# UART_LOGIC.net
KiCad netlist of a schematic drawn in Altium Designer
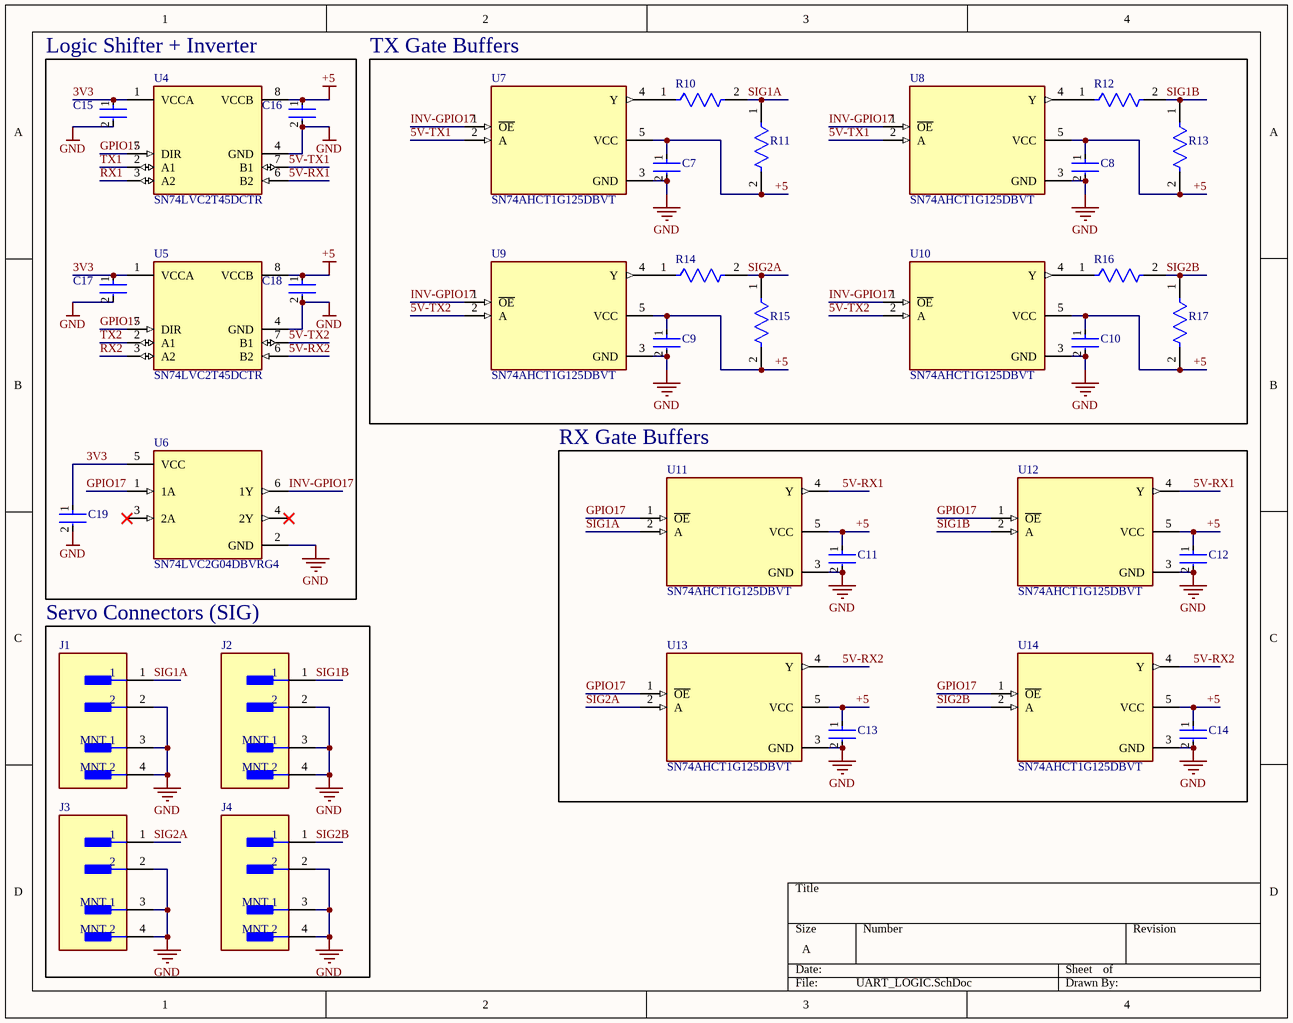
[diagram p0: UART_LOGIC.SchDoc]

(export (version "E")
  (design (tool "Eeschema 10.0.6"))
  (components
    (comp (ref "C7")
      (value "CC0805KRX7R9BB104")
      (footprint "FP-CC0805-0_85-MFG")
      (description "CAP CER 0.1UF 50V X7R 0805")
      (fields (field (name "TOLERANCE") "0.1") (field (name "MANUFACTURER") "Yageo"))
      (libsource (lib "Altium Content Vault") (part "11868f565c42a9108669ba33697ecf6"))
    )
    (comp (ref "C8")
      (value "CC0805KRX7R9BB104")
      (footprint "FP-CC0805-0_85-MFG")
      (description "CAP CER 0.1UF 50V X7R 0805")
      (fields (field (name "TOLERANCE") "0.1") (field (name "MANUFACTURER") "Yageo"))
      (libsource (lib "Altium Content Vault") (part "11868f565c42a9108669ba33697ecf6"))
    )
    (comp (ref "C9")
      (value "CC0805KRX7R9BB104")
      (footprint "FP-CC0805-0_85-MFG")
      (description "CAP CER 0.1UF 50V X7R 0805")
      (fields (field (name "TOLERANCE") "0.1") (field (name "MANUFACTURER") "Yageo"))
      (libsource (lib "Altium Content Vault") (part "11868f565c42a9108669ba33697ecf6"))
    )
    (comp (ref "C10")
      (value "CC0805KRX7R9BB104")
      (footprint "FP-CC0805-0_85-MFG")
      (description "CAP CER 0.1UF 50V X7R 0805")
      (fields (field (name "TOLERANCE") "0.1") (field (name "MANUFACTURER") "Yageo"))
      (libsource (lib "Altium Content Vault") (part "11868f565c42a9108669ba33697ecf6"))
    )
    (comp (ref "C11")
      (value "CC0805KRX7R9BB104")
      (footprint "FP-CC0805-0_85-MFG")
      (description "CAP CER 0.1UF 50V X7R 0805")
      (fields (field (name "TOLERANCE") "0.1") (field (name "MANUFACTURER") "Yageo"))
      (libsource (lib "Altium Content Vault") (part "11868f565c42a9108669ba33697ecf6"))
    )
    (comp (ref "C12")
      (value "CC0805KRX7R9BB104")
      (footprint "FP-CC0805-0_85-MFG")
      (description "CAP CER 0.1UF 50V X7R 0805")
      (fields (field (name "TOLERANCE") "0.1") (field (name "MANUFACTURER") "Yageo"))
      (libsource (lib "Altium Content Vault") (part "11868f565c42a9108669ba33697ecf6"))
    )
    (comp (ref "C13")
      (value "CC0805KRX7R9BB104")
      (footprint "FP-CC0805-0_85-MFG")
      (description "CAP CER 0.1UF 50V X7R 0805")
      (fields (field (name "TOLERANCE") "0.1") (field (name "MANUFACTURER") "Yageo"))
      (libsource (lib "Altium Content Vault") (part "11868f565c42a9108669ba33697ecf6"))
    )
    (comp (ref "C14")
      (value "CC0805KRX7R9BB104")
      (footprint "FP-CC0805-0_85-MFG")
      (description "CAP CER 0.1UF 50V X7R 0805")
      (fields (field (name "TOLERANCE") "0.1") (field (name "MANUFACTURER") "Yageo"))
      (libsource (lib "Altium Content Vault") (part "11868f565c42a9108669ba33697ecf6"))
    )
    (comp (ref "C15")
      (value "CC0805KRX7R9BB104")
      (footprint "FP-CC0805-0_85-MFG")
      (description "CAP CER 0.1UF 50V X7R 0805")
      (fields (field (name "TOLERANCE") "0.1") (field (name "MANUFACTURER") "Yageo"))
      (libsource (lib "Altium Content Vault") (part "11868f565c42a9108669ba33697ecf6"))
    )
    (comp (ref "C16")
      (value "CC0805KRX7R9BB104")
      (footprint "FP-CC0805-0_85-MFG")
      (description "CAP CER 0.1UF 50V X7R 0805")
      (fields (field (name "TOLERANCE") "0.1") (field (name "MANUFACTURER") "Yageo"))
      (libsource (lib "Altium Content Vault") (part "11868f565c42a9108669ba33697ecf6"))
    )
    (comp (ref "C17")
      (value "CC0805KRX7R9BB104")
      (footprint "FP-CC0805-0_85-MFG")
      (description "CAP CER 0.1UF 50V X7R 0805")
      (fields (field (name "TOLERANCE") "0.1") (field (name "MANUFACTURER") "Yageo"))
      (libsource (lib "Altium Content Vault") (part "11868f565c42a9108669ba33697ecf6"))
    )
    (comp (ref "C18")
      (value "CC0805KRX7R9BB104")
      (footprint "FP-CC0805-0_85-MFG")
      (description "CAP CER 0.1UF 50V X7R 0805")
      (fields (field (name "TOLERANCE") "0.1") (field (name "MANUFACTURER") "Yageo"))
      (libsource (lib "Altium Content Vault") (part "11868f565c42a9108669ba33697ecf6"))
    )
    (comp (ref "C19")
      (value "CC0805KRX7R9BB104")
      (footprint "FP-CC0805-0_85-MFG")
      (description "CAP CER 0.1UF 50V X7R 0805")
      (fields (field (name "TOLERANCE") "0.1") (field (name "MANUFACTURER") "Yageo"))
      (libsource (lib "Altium Content Vault") (part "11868f565c42a9108669ba33697ecf6"))
    )
    (comp (ref "J1")
      (value "BM02B-SRSS-TBT(LF)(SN)")
      (footprint "FP-BM02B-SRSS-TBT_LF_SN-MFG")
      (description "CONN WIRE HDR 2POS 1MM STSMD")
      (libsource (lib "Altium Content Vault") (part "029478cb6d4f2fad0cd2a245525ee6d"))
    )
    (comp (ref "J2")
      (value "BM02B-SRSS-TBT(LF)(SN)")
      (footprint "FP-BM02B-SRSS-TBT_LF_SN-MFG")
      (description "CONN WIRE HDR 2POS 1MM STSMD")
      (libsource (lib "Altium Content Vault") (part "029478cb6d4f2fad0cd2a245525ee6d"))
    )
    (comp (ref "J3")
      (value "BM02B-SRSS-TBT(LF)(SN)")
      (footprint "FP-BM02B-SRSS-TBT_LF_SN-MFG")
      (description "CONN WIRE HDR 2POS 1MM STSMD")
      (libsource (lib "Altium Content Vault") (part "029478cb6d4f2fad0cd2a245525ee6d"))
    )
    (comp (ref "J4")
      (value "BM02B-SRSS-TBT(LF)(SN)")
      (footprint "FP-BM02B-SRSS-TBT_LF_SN-MFG")
      (description "CONN WIRE HDR 2POS 1MM STSMD")
      (libsource (lib "Altium Content Vault") (part "029478cb6d4f2fad0cd2a245525ee6d"))
    )
    (comp (ref "R10")
      (value "RMCF0603FG47R0")
      (footprint "FP-RMCF0603-IPC_A")
      (description "47Ω ±1% 0.1W 0603 Thick Film Chip Resistor AEC-Q200 compliant")
      (libsource (lib "Altium Content Vault") (part "1029c3af85768c4190bb7ad29bc67b5"))
    )
    (comp (ref "R11")
      (value "RC0603FR-0710KL")
      (footprint "FP-RC0603-0_55-IPC_C")
      (description "RES 10K OHM 1% 1/10W 0603")
      (fields (field (name "TOLERANCE") "1%"))
      (libsource (lib "Altium Content Vault") (part "1029c3af85768c4190bb7ad29bc67b5"))
    )
    (comp (ref "R12")
      (value "RMCF0603FG47R0")
      (footprint "FP-RMCF0603-IPC_A")
      (description "47Ω ±1% 0.1W 0603 Thick Film Chip Resistor AEC-Q200 compliant")
      (libsource (lib "Altium Content Vault") (part "1029c3af85768c4190bb7ad29bc67b5"))
    )
    (comp (ref "R13")
      (value "RC0603FR-0710KL")
      (footprint "FP-RC0603-0_55-IPC_C")
      (description "RES 10K OHM 1% 1/10W 0603")
      (fields (field (name "TOLERANCE") "1%"))
      (libsource (lib "Altium Content Vault") (part "1029c3af85768c4190bb7ad29bc67b5"))
    )
    (comp (ref "R14")
      (value "RMCF0603FG47R0")
      (footprint "FP-RMCF0603-IPC_A")
      (description "47Ω ±1% 0.1W 0603 Thick Film Chip Resistor AEC-Q200 compliant")
      (libsource (lib "Altium Content Vault") (part "1029c3af85768c4190bb7ad29bc67b5"))
    )
    (comp (ref "R15")
      (value "RC0603FR-0710KL")
      (footprint "FP-RC0603-0_55-IPC_C")
      (description "RES 10K OHM 1% 1/10W 0603")
      (fields (field (name "TOLERANCE") "1%"))
      (libsource (lib "Altium Content Vault") (part "1029c3af85768c4190bb7ad29bc67b5"))
    )
    (comp (ref "R16")
      (value "RMCF0603FG47R0")
      (footprint "FP-RMCF0603-IPC_A")
      (description "47Ω ±1% 0.1W 0603 Thick Film Chip Resistor AEC-Q200 compliant")
      (libsource (lib "Altium Content Vault") (part "1029c3af85768c4190bb7ad29bc67b5"))
    )
    (comp (ref "R17")
      (value "RC0603FR-0710KL")
      (footprint "FP-RC0603-0_55-IPC_C")
      (description "RES 10K OHM 1% 1/10W 0603")
      (fields (field (name "TOLERANCE") "1%"))
      (libsource (lib "Altium Content Vault") (part "1029c3af85768c4190bb7ad29bc67b5"))
    )
    (comp (ref "U4")
      (value "SN74LVC2T45DCTR")
      (footprint "FP-DCT0008A-IPC_C")
      (libsource (lib "Bryan Heddle") (part "271d40e9c72c712db4b2912206096bb"))
    )
    (comp (ref "U5")
      (value "SN74LVC2T45DCTR")
      (footprint "FP-DCT0008A-IPC_C")
      (libsource (lib "Bryan Heddle") (part "271d40e9c72c712db4b2912206096bb"))
    )
    (comp (ref "U6")
      (value "SN74LVC2G04DBVRG4")
      (footprint "FP-DBV0006A-MFG")
      (description "IC INVERTER 2CH 2-INP SOT23-6")
      (libsource (lib "Altium Content Vault") (part "9dfbf26b1eab2647ff4a890ff2a17ee"))
    )
    (comp (ref "U7")
      (value "SN74AHCT1G125DBVT")
      (footprint "SOT95P280X145-5N")
      (description "Single 4.5-V to 5.5-V buffer with TTL-compatible CMOS inputs and 3-state outputs")
      (fields (field (name "MF") "Texas Instruments"))
      (libsource (lib "Bryan Heddle") (part "SN74AHCT1G125DBVT"))
    )
    (comp (ref "U8")
      (value "SN74AHCT1G125DBVT")
      (footprint "SOT95P280X145-5N")
      (description "Single 4.5-V to 5.5-V buffer with TTL-compatible CMOS inputs and 3-state outputs")
      (fields (field (name "MF") "Texas Instruments"))
      (libsource (lib "Bryan Heddle") (part "SN74AHCT1G125DBVT"))
    )
    (comp (ref "U9")
      (value "SN74AHCT1G125DBVT")
      (footprint "SOT95P280X145-5N")
      (description "Single 4.5-V to 5.5-V buffer with TTL-compatible CMOS inputs and 3-state outputs")
      (fields (field (name "MF") "Texas Instruments"))
      (libsource (lib "Bryan Heddle") (part "SN74AHCT1G125DBVT"))
    )
    (comp (ref "U10")
      (value "SN74AHCT1G125DBVT")
      (footprint "SOT95P280X145-5N")
      (description "Single 4.5-V to 5.5-V buffer with TTL-compatible CMOS inputs and 3-state outputs")
      (fields (field (name "MF") "Texas Instruments"))
      (libsource (lib "Bryan Heddle") (part "SN74AHCT1G125DBVT"))
    )
    (comp (ref "U11")
      (value "SN74AHCT1G125DBVT")
      (footprint "SOT95P280X145-5N")
      (description "Single 4.5-V to 5.5-V buffer with TTL-compatible CMOS inputs and 3-state outputs")
      (fields (field (name "MF") "Texas Instruments"))
      (libsource (lib "Bryan Heddle") (part "SN74AHCT1G125DBVT"))
    )
    (comp (ref "U12")
      (value "SN74AHCT1G125DBVT")
      (footprint "SOT95P280X145-5N")
      (description "Single 4.5-V to 5.5-V buffer with TTL-compatible CMOS inputs and 3-state outputs")
      (fields (field (name "MF") "Texas Instruments"))
      (libsource (lib "Bryan Heddle") (part "SN74AHCT1G125DBVT"))
    )
    (comp (ref "U13")
      (value "SN74AHCT1G125DBVT")
      (footprint "SOT95P280X145-5N")
      (description "Single 4.5-V to 5.5-V buffer with TTL-compatible CMOS inputs and 3-state outputs")
      (fields (field (name "MF") "Texas Instruments"))
      (libsource (lib "Bryan Heddle") (part "SN74AHCT1G125DBVT"))
    )
    (comp (ref "U14")
      (value "SN74AHCT1G125DBVT")
      (footprint "SOT95P280X145-5N")
      (description "Single 4.5-V to 5.5-V buffer with TTL-compatible CMOS inputs and 3-state outputs")
      (fields (field (name "MF") "Texas Instruments"))
      (libsource (lib "Bryan Heddle") (part "SN74AHCT1G125DBVT"))
    )
  )
  (nets
    (net (code "1") (name "+5") (class "Default")
      (node (ref "C10") (pin "1") (pinfunction "1_1") (pintype "passive"))
      (node (ref "C11") (pin "1") (pinfunction "1_1") (pintype "passive"))
      (node (ref "C12") (pin "1") (pinfunction "1_1") (pintype "passive"))
      (node (ref "C13") (pin "1") (pinfunction "1_1") (pintype "passive"))
      (node (ref "C14") (pin "1") (pinfunction "1_1") (pintype "passive"))
      (node (ref "C16") (pin "1") (pinfunction "1_1") (pintype "passive"))
      (node (ref "C18") (pin "1") (pinfunction "1_1") (pintype "passive"))
      (node (ref "C7") (pin "1") (pinfunction "1_1") (pintype "passive"))
      (node (ref "C8") (pin "1") (pinfunction "1_1") (pintype "passive"))
      (node (ref "C9") (pin "1") (pinfunction "1_1") (pintype "passive"))
      (node (ref "R11") (pin "2") (pinfunction "2_2") (pintype "passive"))
      (node (ref "R13") (pin "2") (pinfunction "2_2") (pintype "passive"))
      (node (ref "R15") (pin "2") (pinfunction "2_2") (pintype "passive"))
      (node (ref "R17") (pin "2") (pinfunction "2_2") (pintype "passive"))
      (node (ref "U10") (pin "5") (pinfunction "VCC_5") (pintype "power_in"))
      (node (ref "U11") (pin "5") (pinfunction "VCC_5") (pintype "power_in"))
      (node (ref "U12") (pin "5") (pinfunction "VCC_5") (pintype "power_in"))
      (node (ref "U13") (pin "5") (pinfunction "VCC_5") (pintype "power_in"))
      (node (ref "U14") (pin "5") (pinfunction "VCC_5") (pintype "power_in"))
      (node (ref "U4") (pin "8") (pinfunction "VCCB_8") (pintype "power_in"))
      (node (ref "U5") (pin "8") (pinfunction "VCCB_8") (pintype "power_in"))
      (node (ref "U7") (pin "5") (pinfunction "VCC_5") (pintype "power_in"))
      (node (ref "U8") (pin "5") (pinfunction "VCC_5") (pintype "power_in"))
      (node (ref "U9") (pin "5") (pinfunction "VCC_5") (pintype "power_in"))
    )
    (net (code "2") (name "/3V3") (class "Default")
      (node (ref "C15") (pin "1") (pinfunction "1_1") (pintype "passive"))
      (node (ref "C17") (pin "1") (pinfunction "1_1") (pintype "passive"))
      (node (ref "C19") (pin "1") (pinfunction "1_1") (pintype "passive"))
      (node (ref "U4") (pin "1") (pinfunction "VCCA_1") (pintype "power_in"))
      (node (ref "U5") (pin "1") (pinfunction "VCCA_1") (pintype "power_in"))
      (node (ref "U6") (pin "5") (pinfunction "VCC_5") (pintype "power_in"))
    )
    (net (code "3") (name "/5V-RX1") (class "Default")
      (node (ref "U11") (pin "4") (pinfunction "Y_4") (pintype "output"))
      (node (ref "U12") (pin "4") (pinfunction "Y_4") (pintype "output"))
      (node (ref "U4") (pin "6") (pinfunction "B2_6") (pintype "input"))
    )
    (net (code "4") (name "/5V-RX2") (class "Default")
      (node (ref "U13") (pin "4") (pinfunction "Y_4") (pintype "output"))
      (node (ref "U14") (pin "4") (pinfunction "Y_4") (pintype "output"))
      (node (ref "U5") (pin "6") (pinfunction "B2_6") (pintype "input"))
    )
    (net (code "5") (name "/5V-TX1") (class "Default")
      (node (ref "U4") (pin "7") (pinfunction "B1_7") (pintype "bidirectional"))
      (node (ref "U7") (pin "2") (pinfunction "A_2") (pintype "input"))
      (node (ref "U8") (pin "2") (pinfunction "A_2") (pintype "input"))
    )
    (net (code "6") (name "/5V-TX2") (class "Default")
      (node (ref "U10") (pin "2") (pinfunction "A_2") (pintype "input"))
      (node (ref "U5") (pin "7") (pinfunction "B1_7") (pintype "bidirectional"))
      (node (ref "U9") (pin "2") (pinfunction "A_2") (pintype "input"))
    )
    (net (code "7") (name "/GPIO17") (class "Default")
      (node (ref "U11") (pin "1") (pinfunction "~{OE}_1") (pintype "input"))
      (node (ref "U12") (pin "1") (pinfunction "~{OE}_1") (pintype "input"))
      (node (ref "U13") (pin "1") (pinfunction "~{OE}_1") (pintype "input"))
      (node (ref "U14") (pin "1") (pinfunction "~{OE}_1") (pintype "input"))
      (node (ref "U4") (pin "5") (pinfunction "DIR_5") (pintype "input"))
      (node (ref "U5") (pin "5") (pinfunction "DIR_5") (pintype "input"))
      (node (ref "U6") (pin "1") (pinfunction "1A_1") (pintype "input"))
    )
    (net (code "8") (name "/INV-GPIO17") (class "Default")
      (node (ref "U10") (pin "1") (pinfunction "~{OE}_1") (pintype "input"))
      (node (ref "U6") (pin "6") (pinfunction "1Y_6") (pintype "output"))
      (node (ref "U7") (pin "1") (pinfunction "~{OE}_1") (pintype "input"))
      (node (ref "U8") (pin "1") (pinfunction "~{OE}_1") (pintype "input"))
      (node (ref "U9") (pin "1") (pinfunction "~{OE}_1") (pintype "input"))
    )
    (net (code "9") (name "/RX1") (class "Default")
      (node (ref "U4") (pin "3") (pinfunction "A2_3") (pintype "bidirectional"))
    )
    (net (code "10") (name "/RX2") (class "Default")
      (node (ref "U5") (pin "3") (pinfunction "A2_3") (pintype "bidirectional"))
    )
    (net (code "11") (name "/SIG1A") (class "Default")
      (node (ref "J1") (pin "1") (pinfunction "1_1") (pintype "passive"))
      (node (ref "R10") (pin "2") (pinfunction "2_2") (pintype "passive"))
      (node (ref "R11") (pin "1") (pinfunction "1_1") (pintype "passive"))
      (node (ref "U11") (pin "2") (pinfunction "A_2") (pintype "input"))
    )
    (net (code "12") (name "/SIG1B") (class "Default")
      (node (ref "J2") (pin "1") (pinfunction "1_1") (pintype "passive"))
      (node (ref "R12") (pin "2") (pinfunction "2_2") (pintype "passive"))
      (node (ref "R13") (pin "1") (pinfunction "1_1") (pintype "passive"))
      (node (ref "U12") (pin "2") (pinfunction "A_2") (pintype "input"))
    )
    (net (code "13") (name "/SIG2A") (class "Default")
      (node (ref "J3") (pin "1") (pinfunction "1_1") (pintype "passive"))
      (node (ref "R14") (pin "2") (pinfunction "2_2") (pintype "passive"))
      (node (ref "R15") (pin "1") (pinfunction "1_1") (pintype "passive"))
      (node (ref "U13") (pin "2") (pinfunction "A_2") (pintype "input"))
    )
    (net (code "14") (name "/SIG2B") (class "Default")
      (node (ref "J4") (pin "1") (pinfunction "1_1") (pintype "passive"))
      (node (ref "R16") (pin "2") (pinfunction "2_2") (pintype "passive"))
      (node (ref "R17") (pin "1") (pinfunction "1_1") (pintype "passive"))
      (node (ref "U14") (pin "2") (pinfunction "A_2") (pintype "input"))
    )
    (net (code "15") (name "/TX1") (class "Default")
      (node (ref "U4") (pin "2") (pinfunction "A1_2") (pintype "bidirectional"))
    )
    (net (code "16") (name "/TX2") (class "Default")
      (node (ref "U5") (pin "2") (pinfunction "A1_2") (pintype "bidirectional"))
    )
    (net (code "17") (name "GND") (class "Default")
      (node (ref "C10") (pin "2") (pinfunction "2_2") (pintype "passive"))
      (node (ref "C11") (pin "2") (pinfunction "2_2") (pintype "passive"))
      (node (ref "C12") (pin "2") (pinfunction "2_2") (pintype "passive"))
      (node (ref "C13") (pin "2") (pinfunction "2_2") (pintype "passive"))
      (node (ref "C14") (pin "2") (pinfunction "2_2") (pintype "passive"))
      (node (ref "C15") (pin "2") (pinfunction "2_2") (pintype "passive"))
      (node (ref "C16") (pin "2") (pinfunction "2_2") (pintype "passive"))
      (node (ref "C17") (pin "2") (pinfunction "2_2") (pintype "passive"))
      (node (ref "C18") (pin "2") (pinfunction "2_2") (pintype "passive"))
      (node (ref "C19") (pin "2") (pinfunction "2_2") (pintype "passive"))
      (node (ref "C7") (pin "2") (pinfunction "2_2") (pintype "passive"))
      (node (ref "C8") (pin "2") (pinfunction "2_2") (pintype "passive"))
      (node (ref "C9") (pin "2") (pinfunction "2_2") (pintype "passive"))
      (node (ref "J1") (pin "2") (pinfunction "2_2") (pintype "passive"))
      (node (ref "J1") (pin "3") (pinfunction "MNT_1_3") (pintype "passive"))
      (node (ref "J1") (pin "4") (pinfunction "MNT_2_4") (pintype "passive"))
      (node (ref "J2") (pin "2") (pinfunction "2_2") (pintype "passive"))
      (node (ref "J2") (pin "3") (pinfunction "MNT_1_3") (pintype "passive"))
      (node (ref "J2") (pin "4") (pinfunction "MNT_2_4") (pintype "passive"))
      (node (ref "J3") (pin "2") (pinfunction "2_2") (pintype "passive"))
      (node (ref "J3") (pin "3") (pinfunction "MNT_1_3") (pintype "passive"))
      (node (ref "J3") (pin "4") (pinfunction "MNT_2_4") (pintype "passive"))
      (node (ref "J4") (pin "2") (pinfunction "2_2") (pintype "passive"))
      (node (ref "J4") (pin "3") (pinfunction "MNT_1_3") (pintype "passive"))
      (node (ref "J4") (pin "4") (pinfunction "MNT_2_4") (pintype "passive"))
      (node (ref "U10") (pin "3") (pinfunction "GND_3") (pintype "power_in"))
      (node (ref "U11") (pin "3") (pinfunction "GND_3") (pintype "power_in"))
      (node (ref "U12") (pin "3") (pinfunction "GND_3") (pintype "power_in"))
      (node (ref "U13") (pin "3") (pinfunction "GND_3") (pintype "power_in"))
      (node (ref "U14") (pin "3") (pinfunction "GND_3") (pintype "power_in"))
      (node (ref "U4") (pin "4") (pinfunction "GND_4") (pintype "power_in"))
      (node (ref "U5") (pin "4") (pinfunction "GND_4") (pintype "power_in"))
      (node (ref "U6") (pin "2") (pinfunction "GND_2") (pintype "power_in"))
      (node (ref "U7") (pin "3") (pinfunction "GND_3") (pintype "power_in"))
      (node (ref "U8") (pin "3") (pinfunction "GND_3") (pintype "power_in"))
      (node (ref "U9") (pin "3") (pinfunction "GND_3") (pintype "power_in"))
    )
    (net (code "18") (name "Net-(U7-Y)") (class "Default")
      (node (ref "R10") (pin "1") (pinfunction "1_1") (pintype "passive"))
      (node (ref "U7") (pin "4") (pinfunction "Y_4") (pintype "output"))
    )
    (net (code "19") (name "Net-(U8-Y)") (class "Default")
      (node (ref "R12") (pin "1") (pinfunction "1_1") (pintype "passive"))
      (node (ref "U8") (pin "4") (pinfunction "Y_4") (pintype "output"))
    )
    (net (code "20") (name "Net-(U9-Y)") (class "Default")
      (node (ref "R14") (pin "1") (pinfunction "1_1") (pintype "passive"))
      (node (ref "U9") (pin "4") (pinfunction "Y_4") (pintype "output"))
    )
    (net (code "21") (name "Net-(U10-Y)") (class "Default")
      (node (ref "R16") (pin "1") (pinfunction "1_1") (pintype "passive"))
      (node (ref "U10") (pin "4") (pinfunction "Y_4") (pintype "output"))
    )
    (net (code "22") (name "unconnected-(U6-2A-Pad3)") (class "Default")
      (node (ref "U6") (pin "3") (pinfunction "2A_3") (pintype "input+no_connect"))
    )
    (net (code "23") (name "unconnected-(U6-2Y-Pad4)") (class "Default")
      (node (ref "U6") (pin "4") (pinfunction "2Y_4") (pintype "output+no_connect"))
    )
  )
)
